# zeta2rework_lw_v24_fixes.net
KiCad netlist of a schematic drawn in EAGLE
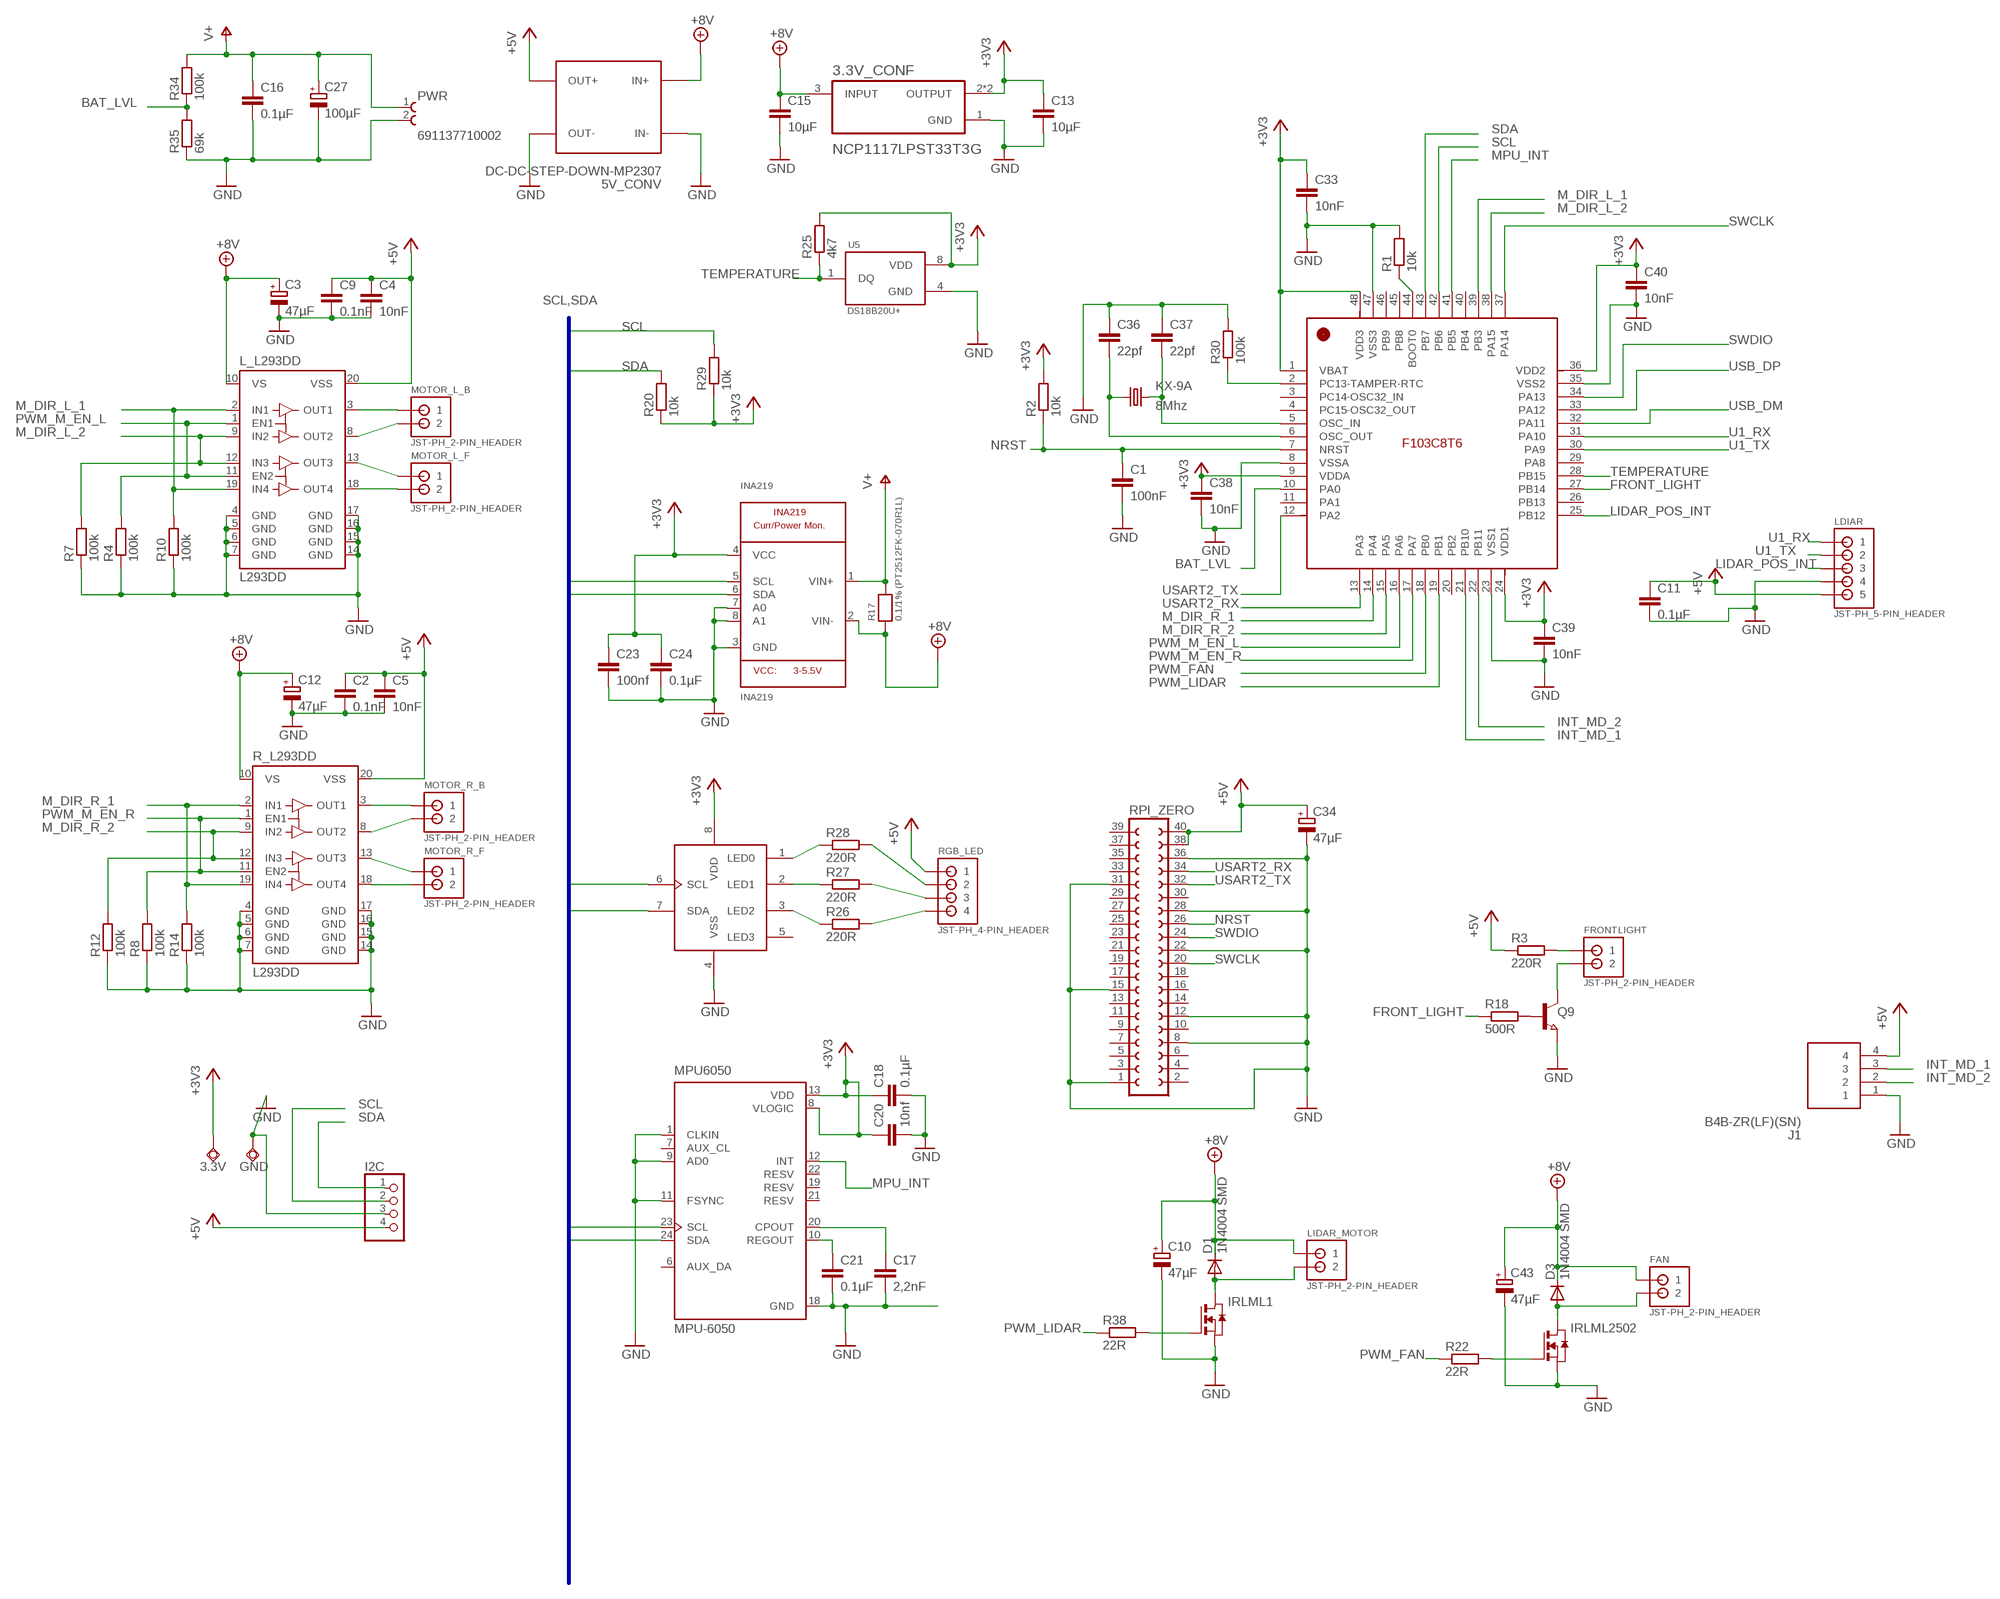
[diagram p0: schematic, sheet 1]

(export (version "E")
  (design (tool "Eeschema 10.0.6"))
  (components
    (comp (ref "3.3V")
      (value "TPSQTP20R")
      (footprint "eagle-import:TP20R")
      (libsource (lib "eagle-import") (part "TPSQTP20R"))
    )
    (comp (ref "3.3V_CONF")
      (value "NCP1117LPST33T3G")
      (footprint "eagle-import:SOT230P700X175-4N")
      (fields (field (name "MF") "ON Semiconductor"))
      (libsource (lib "eagle-import") (part "NCP1117LPST33T3G"))
    )
    (comp (ref "5V_CONV")
      (value "DC-DC-STEP-DOWN-MP2307")
      (footprint "eagle-import:DC-DC-STEP-DOWN-MP2307")
      (libsource (lib "eagle-import") (part "DC-DC-STEP-DOWN-MP2307"))
    )
    (comp (ref "C1")
      (value "100nF")
      (footprint "eagle-import:C1206")
      (libsource (lib "eagle-import") (part "C-EUC1206"))
    )
    (comp (ref "C2")
      (value "0.1nF")
      (footprint "eagle-import:C1206")
      (libsource (lib "eagle-import") (part "C-EUC1206"))
    )
    (comp (ref "C3")
      (value "47µF")
      (footprint "eagle-import:UD-4X5,8_NICHICON")
      (libsource (lib "eagle-import") (part "CPOL-EUUD-4X5,8"))
    )
    (comp (ref "C4")
      (value "10nF")
      (footprint "eagle-import:C1206")
      (libsource (lib "eagle-import") (part "C-EUC1206"))
    )
    (comp (ref "C5")
      (value "10nF")
      (footprint "eagle-import:C1206")
      (libsource (lib "eagle-import") (part "C-EUC1206"))
    )
    (comp (ref "C9")
      (value "0.1nF")
      (footprint "eagle-import:C1206")
      (libsource (lib "eagle-import") (part "C-EUC1206"))
    )
    (comp (ref "C10")
      (value "47µF")
      (footprint "eagle-import:UD-4X5,8_NICHICON")
      (libsource (lib "eagle-import") (part "CPOL-EUUD-4X5,8"))
    )
    (comp (ref "C11")
      (value "0.1µF")
      (footprint "eagle-import:C1206")
      (libsource (lib "eagle-import") (part "C-EUC1206"))
    )
    (comp (ref "C12")
      (value "47µF")
      (footprint "eagle-import:UD-4X5,8_NICHICON")
      (libsource (lib "eagle-import") (part "CPOL-EUUD-4X5,8"))
    )
    (comp (ref "C13")
      (value "10µF")
      (footprint "eagle-import:C1206")
      (libsource (lib "eagle-import") (part "C-EUC1206"))
    )
    (comp (ref "C15")
      (value "10µF")
      (footprint "eagle-import:C1206")
      (libsource (lib "eagle-import") (part "C-EUC1206"))
    )
    (comp (ref "C16")
      (value "0.1µF")
      (footprint "eagle-import:C1206")
      (libsource (lib "eagle-import") (part "C-EUC1206"))
    )
    (comp (ref "C17")
      (value "2,2nF")
      (footprint "eagle-import:C1206")
      (libsource (lib "eagle-import") (part "C-EUC1206"))
    )
    (comp (ref "C18")
      (value "0.1µF")
      (footprint "eagle-import:C1206")
      (libsource (lib "eagle-import") (part "C-EUC1206"))
    )
    (comp (ref "C20")
      (value "10nf")
      (footprint "eagle-import:C1206")
      (libsource (lib "eagle-import") (part "C-EUC1206"))
    )
    (comp (ref "C21")
      (value "0.1µF")
      (footprint "eagle-import:C1206")
      (libsource (lib "eagle-import") (part "C-EUC1206"))
    )
    (comp (ref "C23")
      (value "100nf")
      (footprint "eagle-import:C1206")
      (libsource (lib "eagle-import") (part "C-EUC1206"))
    )
    (comp (ref "C24")
      (value "0.1µF")
      (footprint "eagle-import:C1206")
      (libsource (lib "eagle-import") (part "C-EUC1206"))
    )
    (comp (ref "C27")
      (value "100µF")
      (footprint "eagle-import:UD-4X5,8_NICHICON")
      (libsource (lib "eagle-import") (part "CPOL-EUUD-4X5,8"))
    )
    (comp (ref "C33")
      (value "10nF")
      (footprint "eagle-import:C1206")
      (libsource (lib "eagle-import") (part "C-EUC1206"))
    )
    (comp (ref "C34")
      (value "47µF")
      (footprint "eagle-import:UD-4X5,8_NICHICON")
      (libsource (lib "eagle-import") (part "CPOL-EUUD-4X5,8"))
    )
    (comp (ref "C36")
      (value "22pf")
      (footprint "eagle-import:C1206")
      (libsource (lib "eagle-import") (part "C-EUC1206"))
    )
    (comp (ref "C37")
      (value "22pf")
      (footprint "eagle-import:C1206")
      (libsource (lib "eagle-import") (part "C-EUC1206"))
    )
    (comp (ref "C38")
      (value "10nF")
      (footprint "eagle-import:C1206")
      (libsource (lib "eagle-import") (part "C-EUC1206"))
    )
    (comp (ref "C39")
      (value "10nF")
      (footprint "eagle-import:C1206")
      (libsource (lib "eagle-import") (part "C-EUC1206"))
    )
    (comp (ref "C40")
      (value "10nF")
      (footprint "eagle-import:C1206")
      (libsource (lib "eagle-import") (part "C-EUC1206"))
    )
    (comp (ref "C43")
      (value "47µF")
      (footprint "eagle-import:UD-4X5,8_NICHICON")
      (libsource (lib "eagle-import") (part "CPOL-EUUD-4X5,8"))
    )
    (comp (ref "D1")
      (value "1N4004 SMD")
      (footprint "eagle-import:DO214AC")
      (libsource (lib "eagle-import") (part "DIODE-DO214AC"))
    )
    (comp (ref "D3")
      (value "1N4004 SMD")
      (footprint "eagle-import:DO214AC")
      (libsource (lib "eagle-import") (part "DIODE-DO214AC"))
    )
    (comp (ref "FAN")
      (value "JST-PH_2-PIN_HEADER")
      (footprint "eagle-import:JST_B2B-PH_HEADER")
      (libsource (lib "eagle-import") (part "JST-PH_2-PIN_HEADER"))
    )
    (comp (ref "FRONTLIGHT")
      (value "JST-PH_2-PIN_HEADER")
      (footprint "eagle-import:JST_B2B-PH_HEADER")
      (libsource (lib "eagle-import") (part "JST-PH_2-PIN_HEADER"))
    )
    (comp (ref "GND")
      (value "TPSQTP20R")
      (footprint "eagle-import:TP20R")
      (libsource (lib "eagle-import") (part "TPSQTP20R"))
    )
    (comp (ref "I2C")
      (value "PINHD-1X4")
      (footprint "eagle-import:1X04")
      (libsource (lib "eagle-import") (part "PINHD-1X4"))
    )
    (comp (ref "INA219")
      (value "INA219")
      (footprint "eagle-import:SOT23-8")
      (fields (field (name "MF") "Texas Instruments"))
      (libsource (lib "eagle-import") (part "INA219"))
    )
    (comp (ref "IRLML1")
      (value "NMOSSOT23")
      (footprint "eagle-import:SOT-23")
      (libsource (lib "eagle-import") (part "NMOSSOT23"))
    )
    (comp (ref "IRLML2502")
      (value "NMOSSOT23")
      (footprint "eagle-import:SOT-23")
      (libsource (lib "eagle-import") (part "NMOSSOT23"))
    )
    (comp (ref "J1")
      (value "B4B-ZR(LF)(SN)")
      (footprint "eagle-import:SHDR4W50P0X150_1X4_750X350X450")
      (fields (field (name "FARNELL_PART_NUMBER") "9491791"))
      (libsource (lib "eagle-import") (part "B4B-ZR(LF)(SN)"))
    )
    (comp (ref "KX-9A")
      (value "8Mhz")
      (footprint "eagle-import:5.0X3.2_KX-9A")
      (libsource (lib "eagle-import") (part "KX-9A"))
    )
    (comp (ref "LDIAR")
      (value "JST-PH_5-PIN_HEADER")
      (footprint "eagle-import:JST_B5B-PH_HEADER")
      (libsource (lib "eagle-import") (part "JST-PH_5-PIN_HEADER"))
    )
    (comp (ref "LIDAR_MOTOR")
      (value "JST-PH_2-PIN_HEADER")
      (footprint "eagle-import:JST_B2B-PH_HEADER")
      (libsource (lib "eagle-import") (part "JST-PH_2-PIN_HEADER"))
    )
    (comp (ref "L_L293DD")
      (value "L293DD")
      (footprint "eagle-import:SO20")
      (libsource (lib "eagle-import") (part "L293DD"))
    )
    (comp (ref "MOTOR_L_B")
      (value "JST-PH_2-PIN_HEADER")
      (footprint "eagle-import:JST_B2B-PH_HEADER")
      (libsource (lib "eagle-import") (part "JST-PH_2-PIN_HEADER"))
    )
    (comp (ref "MOTOR_L_F")
      (value "JST-PH_2-PIN_HEADER")
      (footprint "eagle-import:JST_B2B-PH_HEADER")
      (libsource (lib "eagle-import") (part "JST-PH_2-PIN_HEADER"))
    )
    (comp (ref "MOTOR_R_B")
      (value "JST-PH_2-PIN_HEADER")
      (footprint "eagle-import:JST_B2B-PH_HEADER")
      (libsource (lib "eagle-import") (part "JST-PH_2-PIN_HEADER"))
    )
    (comp (ref "MOTOR_R_F")
      (value "JST-PH_2-PIN_HEADER")
      (footprint "eagle-import:JST_B2B-PH_HEADER")
      (libsource (lib "eagle-import") (part "JST-PH_2-PIN_HEADER"))
    )
    (comp (ref "MPU6050")
      (value "MPU-6050")
      (footprint "eagle-import:QFN50P400X400X95-24N")
      (fields (field (name "MF") "TDK"))
      (libsource (lib "eagle-import") (part "MPU-6050"))
    )
    (comp (ref "PCA9533")
      (value "PCA9533")
      (footprint "eagle-import:SOIC8")
      (libsource (lib "eagle-import") (part "PCA9533"))
    )
    (comp (ref "PWR")
      (value "691137710002")
      (footprint "eagle-import:691137710002")
      (fields (field (name "MF") "Wurth Electronics"))
      (libsource (lib "eagle-import") (part "691137710002"))
    )
    (comp (ref "Q9")
      (value "NPN-TRANSISTOR_SOT23")
      (footprint "eagle-import:SOT23")
      (libsource (lib "eagle-import") (part "NPN-TRANSISTOR_SOT23"))
    )
    (comp (ref "R1")
      (value "10k")
      (footprint "eagle-import:R0603")
      (libsource (lib "eagle-import") (part "R-EU_R0603"))
    )
    (comp (ref "R2")
      (value "10k")
      (footprint "eagle-import:R0603")
      (libsource (lib "eagle-import") (part "R-EU_R0603"))
    )
    (comp (ref "R3")
      (value "220R")
      (footprint "eagle-import:R0603")
      (libsource (lib "eagle-import") (part "R-EU_R0603"))
    )
    (comp (ref "R4")
      (value "100k")
      (footprint "eagle-import:R0603")
      (libsource (lib "eagle-import") (part "R-EU_R0603"))
    )
    (comp (ref "R7")
      (value "100k")
      (footprint "eagle-import:R0603")
      (libsource (lib "eagle-import") (part "R-EU_R0603"))
    )
    (comp (ref "R8")
      (value "100k")
      (footprint "eagle-import:R0603")
      (libsource (lib "eagle-import") (part "R-EU_R0603"))
    )
    (comp (ref "R10")
      (value "100k")
      (footprint "eagle-import:R0603")
      (libsource (lib "eagle-import") (part "R-EU_R0603"))
    )
    (comp (ref "R12")
      (value "100k")
      (footprint "eagle-import:R0603")
      (libsource (lib "eagle-import") (part "R-EU_R0603"))
    )
    (comp (ref "R14")
      (value "100k")
      (footprint "eagle-import:R0603")
      (libsource (lib "eagle-import") (part "R-EU_R0603"))
    )
    (comp (ref "R17")
      (value "0.1/1% (PT2512FK-070R1L)")
      (footprint "eagle-import:2512")
      (libsource (lib "eagle-import") (part "RESISTOR2512"))
    )
    (comp (ref "R18")
      (value "500R")
      (footprint "eagle-import:R0603")
      (libsource (lib "eagle-import") (part "R-EU_R0603"))
    )
    (comp (ref "R20")
      (value "10k")
      (footprint "eagle-import:R0603")
      (libsource (lib "eagle-import") (part "R-EU_R0603"))
    )
    (comp (ref "R22")
      (value "22R")
      (footprint "eagle-import:R0603")
      (libsource (lib "eagle-import") (part "R-EU_R0603"))
    )
    (comp (ref "R25")
      (value "4k7")
      (footprint "eagle-import:R0603")
      (libsource (lib "eagle-import") (part "R-EU_R0603"))
    )
    (comp (ref "R26")
      (value "220R")
      (footprint "eagle-import:R0603")
      (libsource (lib "eagle-import") (part "R-EU_R0603"))
    )
    (comp (ref "R27")
      (value "220R")
      (footprint "eagle-import:R0603")
      (libsource (lib "eagle-import") (part "R-EU_R0603"))
    )
    (comp (ref "R28")
      (value "220R")
      (footprint "eagle-import:R0603")
      (libsource (lib "eagle-import") (part "R-EU_R0603"))
    )
    (comp (ref "R29")
      (value "10k")
      (footprint "eagle-import:R0603")
      (libsource (lib "eagle-import") (part "R-EU_R0603"))
    )
    (comp (ref "R30")
      (value "100k")
      (footprint "eagle-import:R0603")
      (libsource (lib "eagle-import") (part "R-EU_R0603"))
    )
    (comp (ref "R34")
      (value "100k")
      (footprint "eagle-import:R0603")
      (libsource (lib "eagle-import") (part "R-EU_R0603"))
    )
    (comp (ref "R35")
      (value "69k")
      (footprint "eagle-import:R0603")
      (libsource (lib "eagle-import") (part "R-EU_R0603"))
    )
    (comp (ref "R38")
      (value "22R")
      (footprint "eagle-import:R0603")
      (libsource (lib "eagle-import") (part "R-EU_R0603"))
    )
    (comp (ref "RGB_LED")
      (value "JST-PH_4-PIN_HEADER")
      (footprint "eagle-import:JST_B4B-PH_HEADER")
      (libsource (lib "eagle-import") (part "JST-PH_4-PIN_HEADER"))
    )
    (comp (ref "RPI_ZERO")
      (value "FE20-2")
      (footprint "eagle-import:FE20-2")
      (libsource (lib "eagle-import") (part "FE20-2"))
    )
    (comp (ref "R_L293DD")
      (value "L293DD")
      (footprint "eagle-import:SO20")
      (libsource (lib "eagle-import") (part "L293DD"))
    )
    (comp (ref "STM32F103CB")
      (value "STM32F103CB")
      (footprint "eagle-import:LQFP48_7X7MM_0.5MMPP")
      (fields (field (name "MF") "STMicroelectronics") (field (name "MP") "STM32F103C8T6"))
      (libsource (lib "eagle-import") (part "STM32F103C8T6"))
    )
    (comp (ref "U5")
      (value "DS18B20U+")
      (footprint "eagle-import:SOP65P490X95-8N")
      (fields (field (name "MF") "Maxim"))
      (libsource (lib "eagle-import") (part "DS18B20U+"))
    )
  )
  (nets
    (net (code "1") (name "+3V3") (class "Default")
      (node (ref "3.3V") (pin "TP") (pinfunction "TP_TP") (pintype "input"))
      (node (ref "3.3V_CONF") (pin "2") (pinfunction "OUTPUT_2") (pintype "output"))
      (node (ref "3.3V_CONF") (pin "4") (pinfunction "OUTPUT_4") (pintype "output"))
      (node (ref "C13") (pin "1") (pinfunction "1_1") (pintype "passive"))
      (node (ref "C18") (pin "1") (pinfunction "1_1") (pintype "passive"))
      (node (ref "C20") (pin "1") (pinfunction "1_1") (pintype "passive"))
      (node (ref "C23") (pin "1") (pinfunction "1_1") (pintype "passive"))
      (node (ref "C24") (pin "1") (pinfunction "1_1") (pintype "passive"))
      (node (ref "C33") (pin "1") (pinfunction "1_1") (pintype "passive"))
      (node (ref "C38") (pin "1") (pinfunction "1_1") (pintype "passive"))
      (node (ref "C39") (pin "1") (pinfunction "1_1") (pintype "passive"))
      (node (ref "C40") (pin "1") (pinfunction "1_1") (pintype "passive"))
      (node (ref "INA219") (pin "4") (pinfunction "VCC_4") (pintype "bidirectional"))
      (node (ref "MPU6050") (pin "13") (pinfunction "VDD_13") (pintype "power_in"))
      (node (ref "MPU6050") (pin "8") (pinfunction "VLOGIC_8") (pintype "power_in"))
      (node (ref "PCA9533") (pin "8") (pinfunction "VDD_8") (pintype "power_in"))
      (node (ref "R2") (pin "2") (pinfunction "2_2") (pintype "passive"))
      (node (ref "R20") (pin "1") (pinfunction "1_1") (pintype "passive"))
      (node (ref "R25") (pin "2") (pinfunction "2_2") (pintype "passive"))
      (node (ref "R29") (pin "1") (pinfunction "1_1") (pintype "passive"))
      (node (ref "STM32F103CB") (pin "1") (pinfunction "VBAT_1") (pintype "bidirectional"))
      (node (ref "STM32F103CB") (pin "24") (pinfunction "VDD1_24") (pintype "bidirectional"))
      (node (ref "STM32F103CB") (pin "36") (pinfunction "VDD2_36") (pintype "bidirectional"))
      (node (ref "STM32F103CB") (pin "48") (pinfunction "VDD3_48") (pintype "bidirectional"))
      (node (ref "STM32F103CB") (pin "9") (pinfunction "VDDA_9") (pintype "bidirectional"))
      (node (ref "U5") (pin "8") (pinfunction "VDD_8") (pintype "power_in"))
    )
    (net (code "2") (name "+5V") (class "Default")
      (node (ref "5V_CONV") (pin "OUT+") (pinfunction "OUT+_OUT+") (pintype "bidirectional"))
      (node (ref "C11") (pin "1") (pinfunction "1_1") (pintype "passive"))
      (node (ref "C2") (pin "1") (pinfunction "1_1") (pintype "passive"))
      (node (ref "C34") (pin "+") (pinfunction "+_+") (pintype "passive"))
      (node (ref "C4") (pin "1") (pinfunction "1_1") (pintype "passive"))
      (node (ref "C5") (pin "1") (pinfunction "1_1") (pintype "passive"))
      (node (ref "C9") (pin "1") (pinfunction "1_1") (pintype "passive"))
      (node (ref "I2C") (pin "4") (pinfunction "4_4") (pintype "passive"))
      (node (ref "J1") (pin "4") (pinfunction "4_4") (pintype "bidirectional"))
      (node (ref "LDIAR") (pin "P5") (pinfunction "5_P5") (pintype "bidirectional"))
      (node (ref "L_L293DD") (pin "20") (pinfunction "VSS_20") (pintype "power_in"))
      (node (ref "R3") (pin "1") (pinfunction "1_1") (pintype "passive"))
      (node (ref "RGB_LED") (pin "P1") (pinfunction "1_P1") (pintype "bidirectional"))
      (node (ref "RPI_ZERO") (pin "38") (pinfunction "38_38") (pintype "passive"))
      (node (ref "RPI_ZERO") (pin "40") (pinfunction "40_40") (pintype "passive"))
      (node (ref "R_L293DD") (pin "20") (pinfunction "VSS_20") (pintype "power_in"))
    )
    (net (code "3") (name "+8V") (class "Default")
      (node (ref "3.3V_CONF") (pin "3") (pinfunction "INPUT_3") (pintype "input"))
      (node (ref "5V_CONV") (pin "IN+") (pinfunction "IN+_IN+") (pintype "bidirectional"))
      (node (ref "C10") (pin "+") (pinfunction "+_+") (pintype "passive"))
      (node (ref "C12") (pin "+") (pinfunction "+_+") (pintype "passive"))
      (node (ref "C15") (pin "1") (pinfunction "1_1") (pintype "passive"))
      (node (ref "C3") (pin "+") (pinfunction "+_+") (pintype "passive"))
      (node (ref "C43") (pin "+") (pinfunction "+_+") (pintype "passive"))
      (node (ref "D1") (pin "C") (pinfunction "C_C") (pintype "passive"))
      (node (ref "D3") (pin "C") (pinfunction "C_C") (pintype "passive"))
      (node (ref "FAN") (pin "P1") (pinfunction "1_P1") (pintype "bidirectional"))
      (node (ref "INA219") (pin "2") (pinfunction "VIN-_2") (pintype "bidirectional"))
      (node (ref "LIDAR_MOTOR") (pin "P1") (pinfunction "1_P1") (pintype "bidirectional"))
      (node (ref "L_L293DD") (pin "10") (pinfunction "VS_10") (pintype "power_in"))
      (node (ref "R17") (pin "1") (pinfunction "1_1") (pintype "passive"))
      (node (ref "R_L293DD") (pin "10") (pinfunction "VS_10") (pintype "power_in"))
    )
    (net (code "4") (name "/BAT_LVL") (class "Default")
      (node (ref "R34") (pin "1") (pinfunction "1_1") (pintype "passive"))
      (node (ref "R35") (pin "2") (pinfunction "2_2") (pintype "passive"))
      (node (ref "STM32F103CB") (pin "10") (pinfunction "PA0_10") (pintype "bidirectional"))
    )
    (net (code "5") (name "/FRONT_LIGHT") (class "Default")
      (node (ref "R18") (pin "1") (pinfunction "1_1") (pintype "passive"))
      (node (ref "STM32F103CB") (pin "27") (pinfunction "PB14_27") (pintype "bidirectional"))
    )
    (net (code "6") (name "/INT_MD_1") (class "Default")
      (node (ref "J1") (pin "3") (pinfunction "3_3") (pintype "bidirectional"))
      (node (ref "STM32F103CB") (pin "21") (pinfunction "PB10_21") (pintype "bidirectional"))
    )
    (net (code "7") (name "/INT_MD_2") (class "Default")
      (node (ref "J1") (pin "2") (pinfunction "2_2") (pintype "bidirectional"))
      (node (ref "STM32F103CB") (pin "22") (pinfunction "PB11_22") (pintype "bidirectional"))
    )
    (net (code "8") (name "/LIDAR_POS_INT") (class "Default")
      (node (ref "LDIAR") (pin "P3") (pinfunction "3_P3") (pintype "bidirectional"))
      (node (ref "STM32F103CB") (pin "25") (pinfunction "PB12_25") (pintype "bidirectional"))
    )
    (net (code "9") (name "/MPU_INT") (class "Default")
      (node (ref "MPU6050") (pin "12") (pinfunction "INT_12") (pintype "output"))
      (node (ref "STM32F103CB") (pin "41") (pinfunction "PB5_41") (pintype "bidirectional"))
    )
    (net (code "10") (name "/M_DIR_L_1") (class "Default")
      (node (ref "L_L293DD") (pin "19") (pinfunction "IN4_19") (pintype "input"))
      (node (ref "L_L293DD") (pin "2") (pinfunction "IN1_2") (pintype "input"))
      (node (ref "R10") (pin "2") (pinfunction "2_2") (pintype "passive"))
      (node (ref "STM32F103CB") (pin "39") (pinfunction "PB3_39") (pintype "bidirectional"))
    )
    (net (code "11") (name "/M_DIR_L_2") (class "Default")
      (node (ref "L_L293DD") (pin "12") (pinfunction "IN3_12") (pintype "input"))
      (node (ref "L_L293DD") (pin "9") (pinfunction "IN2_9") (pintype "input"))
      (node (ref "R7") (pin "2") (pinfunction "2_2") (pintype "passive"))
      (node (ref "STM32F103CB") (pin "38") (pinfunction "PA15_38") (pintype "bidirectional"))
    )
    (net (code "12") (name "/M_DIR_R_1") (class "Default")
      (node (ref "R14") (pin "2") (pinfunction "2_2") (pintype "passive"))
      (node (ref "R_L293DD") (pin "19") (pinfunction "IN4_19") (pintype "input"))
      (node (ref "R_L293DD") (pin "2") (pinfunction "IN1_2") (pintype "input"))
      (node (ref "STM32F103CB") (pin "14") (pinfunction "PA4_14") (pintype "bidirectional"))
    )
    (net (code "13") (name "/M_DIR_R_2") (class "Default")
      (node (ref "R12") (pin "2") (pinfunction "2_2") (pintype "passive"))
      (node (ref "R_L293DD") (pin "12") (pinfunction "IN3_12") (pintype "input"))
      (node (ref "R_L293DD") (pin "9") (pinfunction "IN2_9") (pintype "input"))
      (node (ref "STM32F103CB") (pin "15") (pinfunction "PA5_15") (pintype "bidirectional"))
    )
    (net (code "14") (name "/NRST") (class "Default")
      (node (ref "C1") (pin "1") (pinfunction "1_1") (pintype "passive"))
      (node (ref "R2") (pin "1") (pinfunction "1_1") (pintype "passive"))
      (node (ref "RPI_ZERO") (pin "26") (pinfunction "26_26") (pintype "passive"))
      (node (ref "STM32F103CB") (pin "7") (pinfunction "NRST_7") (pintype "bidirectional"))
    )
    (net (code "15") (name "/PWM_FAN") (class "Default")
      (node (ref "R22") (pin "1") (pinfunction "1_1") (pintype "passive"))
      (node (ref "STM32F103CB") (pin "18") (pinfunction "PB0_18") (pintype "bidirectional"))
    )
    (net (code "16") (name "/PWM_LIDAR") (class "Default")
      (node (ref "R38") (pin "1") (pinfunction "1_1") (pintype "passive"))
      (node (ref "STM32F103CB") (pin "19") (pinfunction "PB1_19") (pintype "bidirectional"))
    )
    (net (code "17") (name "/PWM_M_EN_L") (class "Default")
      (node (ref "L_L293DD") (pin "1") (pinfunction "EN1_1") (pintype "input"))
      (node (ref "L_L293DD") (pin "11") (pinfunction "EN2_11") (pintype "input"))
      (node (ref "R4") (pin "2") (pinfunction "2_2") (pintype "passive"))
      (node (ref "STM32F103CB") (pin "16") (pinfunction "PA6_16") (pintype "bidirectional"))
    )
    (net (code "18") (name "/PWM_M_EN_R") (class "Default")
      (node (ref "R8") (pin "2") (pinfunction "2_2") (pintype "passive"))
      (node (ref "R_L293DD") (pin "1") (pinfunction "EN1_1") (pintype "input"))
      (node (ref "R_L293DD") (pin "11") (pinfunction "EN2_11") (pintype "input"))
      (node (ref "STM32F103CB") (pin "17") (pinfunction "PA7_17") (pintype "bidirectional"))
    )
    (net (code "19") (name "/SCL") (class "Default")
      (node (ref "I2C") (pin "2") (pinfunction "2_2") (pintype "passive"))
      (node (ref "INA219") (pin "5") (pinfunction "SCL_5") (pintype "bidirectional"))
      (node (ref "MPU6050") (pin "23") (pinfunction "SCL_23") (pintype "input"))
      (node (ref "PCA9533") (pin "6") (pinfunction "SCL_6") (pintype "input"))
      (node (ref "R29") (pin "2") (pinfunction "2_2") (pintype "passive"))
      (node (ref "STM32F103CB") (pin "42") (pinfunction "PB6_42") (pintype "bidirectional"))
    )
    (net (code "20") (name "/SDA") (class "Default")
      (node (ref "I2C") (pin "1") (pinfunction "1_1") (pintype "passive"))
      (node (ref "INA219") (pin "6") (pinfunction "SDA_6") (pintype "bidirectional"))
      (node (ref "MPU6050") (pin "24") (pinfunction "SDA_24") (pintype "bidirectional"))
      (node (ref "PCA9533") (pin "7") (pinfunction "SDA_7") (pintype "bidirectional"))
      (node (ref "R20") (pin "2") (pinfunction "2_2") (pintype "passive"))
      (node (ref "STM32F103CB") (pin "43") (pinfunction "PB7_43") (pintype "bidirectional"))
    )
    (net (code "21") (name "/SWCLK") (class "Default")
      (node (ref "RPI_ZERO") (pin "20") (pinfunction "20_20") (pintype "passive"))
      (node (ref "STM32F103CB") (pin "37") (pinfunction "PA14_37") (pintype "bidirectional"))
    )
    (net (code "22") (name "/SWDIO") (class "Default")
      (node (ref "RPI_ZERO") (pin "24") (pinfunction "24_24") (pintype "passive"))
      (node (ref "STM32F103CB") (pin "34") (pinfunction "PA13_34") (pintype "bidirectional"))
    )
    (net (code "23") (name "/TEMPERATURE") (class "Default")
      (node (ref "R25") (pin "1") (pinfunction "1_1") (pintype "passive"))
      (node (ref "STM32F103CB") (pin "28") (pinfunction "PB15_28") (pintype "bidirectional"))
      (node (ref "U5") (pin "1") (pinfunction "DQ_1") (pintype "bidirectional"))
    )
    (net (code "24") (name "/U1_RX") (class "Default")
      (node (ref "LDIAR") (pin "P1") (pinfunction "1_P1") (pintype "bidirectional"))
      (node (ref "STM32F103CB") (pin "31") (pinfunction "PA10_31") (pintype "bidirectional"))
    )
    (net (code "25") (name "/U1_TX") (class "Default")
      (node (ref "LDIAR") (pin "P2") (pinfunction "2_P2") (pintype "bidirectional"))
      (node (ref "STM32F103CB") (pin "30") (pinfunction "PA9_30") (pintype "bidirectional"))
    )
    (net (code "26") (name "/USART2_RX") (class "Default")
      (node (ref "RPI_ZERO") (pin "34") (pinfunction "34_34") (pintype "passive"))
      (node (ref "STM32F103CB") (pin "13") (pinfunction "PA3_13") (pintype "bidirectional"))
    )
    (net (code "27") (name "/USART2_TX") (class "Default")
      (node (ref "RPI_ZERO") (pin "32") (pinfunction "32_32") (pintype "passive"))
      (node (ref "STM32F103CB") (pin "12") (pinfunction "PA2_12") (pintype "bidirectional"))
    )
    (net (code "28") (name "/USB_DM") (class "Default")
      (node (ref "STM32F103CB") (pin "32") (pinfunction "PA11_32") (pintype "bidirectional"))
    )
    (net (code "29") (name "/USB_DP") (class "Default")
      (node (ref "STM32F103CB") (pin "33") (pinfunction "PA12_33") (pintype "bidirectional"))
    )
    (net (code "31") (name "GND") (class "Default")
      (node (ref "3.3V_CONF") (pin "1") (pinfunction "GND_1") (pintype "power_in"))
      (node (ref "5V_CONV") (pin "IN-") (pinfunction "IN-_IN-") (pintype "bidirectional"))
      (node (ref "5V_CONV") (pin "OUT-") (pinfunction "OUT-_OUT-") (pintype "bidirectional"))
      (node (ref "C1") (pin "2") (pinfunction "2_2") (pintype "passive"))
      (node (ref "C10") (pin "-") (pinfunction "-_-") (pintype "passive"))
      (node (ref "C11") (pin "2") (pinfunction "2_2") (pintype "passive"))
      (node (ref "C12") (pin "-") (pinfunction "-_-") (pintype "passive"))
      (node (ref "C13") (pin "2") (pinfunction "2_2") (pintype "passive"))
      (node (ref "C15") (pin "2") (pinfunction "2_2") (pintype "passive"))
      (node (ref "C16") (pin "2") (pinfunction "2_2") (pintype "passive"))
      (node (ref "C17") (pin "2") (pinfunction "2_2") (pintype "passive"))
      (node (ref "C18") (pin "2") (pinfunction "2_2") (pintype "passive"))
      (node (ref "C2") (pin "2") (pinfunction "2_2") (pintype "passive"))
      (node (ref "C20") (pin "2") (pinfunction "2_2") (pintype "passive"))
      (node (ref "C21") (pin "2") (pinfunction "2_2") (pintype "passive"))
      (node (ref "C23") (pin "2") (pinfunction "2_2") (pintype "passive"))
      (node (ref "C24") (pin "2") (pinfunction "2_2") (pintype "passive"))
      (node (ref "C27") (pin "-") (pinfunction "-_-") (pintype "passive"))
      (node (ref "C3") (pin "-") (pinfunction "-_-") (pintype "passive"))
      (node (ref "C33") (pin "2") (pinfunction "2_2") (pintype "passive"))
      (node (ref "C34") (pin "-") (pinfunction "-_-") (pintype "passive"))
      (node (ref "C36") (pin "1") (pinfunction "1_1") (pintype "passive"))
      (node (ref "C37") (pin "1") (pinfunction "1_1") (pintype "passive"))
      (node (ref "C38") (pin "2") (pinfunction "2_2") (pintype "passive"))
      (node (ref "C39") (pin "2") (pinfunction "2_2") (pintype "passive"))
      (node (ref "C4") (pin "2") (pinfunction "2_2") (pintype "passive"))
      (node (ref "C40") (pin "2") (pinfunction "2_2") (pintype "passive"))
      (node (ref "C43") (pin "-") (pinfunction "-_-") (pintype "passive"))
      (node (ref "C5") (pin "2") (pinfunction "2_2") (pintype "passive"))
      (node (ref "C9") (pin "2") (pinfunction "2_2") (pintype "passive"))
      (node (ref "GND") (pin "TP") (pinfunction "TP_TP") (pintype "input"))
      (node (ref "I2C") (pin "3") (pinfunction "3_3") (pintype "passive"))
      (node (ref "INA219") (pin "3") (pinfunction "GND_3") (pintype "bidirectional"))
      (node (ref "INA219") (pin "7") (pinfunction "A0_7") (pintype "bidirectional"))
      (node (ref "INA219") (pin "8") (pinfunction "A1_8") (pintype "bidirectional"))
      (node (ref "IRLML1") (pin "2") (pinfunction "S_2") (pintype "passive"))
      (node (ref "IRLML2502") (pin "2") (pinfunction "S_2") (pintype "passive"))
      (node (ref "J1") (pin "1") (pinfunction "1_1") (pintype "bidirectional"))
      (node (ref "LDIAR") (pin "P4") (pinfunction "4_P4") (pintype "bidirectional"))
      (node (ref "L_L293DD") (pin "14") (pinfunction "GND_14") (pintype "power_in"))
      (node (ref "L_L293DD") (pin "15") (pinfunction "GND_15") (pintype "power_in"))
      (node (ref "L_L293DD") (pin "16") (pinfunction "GND_16") (pintype "power_in"))
      (node (ref "L_L293DD") (pin "17") (pinfunction "GND_17") (pintype "power_in"))
      (node (ref "L_L293DD") (pin "4") (pinfunction "GND_4") (pintype "power_in"))
      (node (ref "L_L293DD") (pin "5") (pinfunction "GND_5") (pintype "power_in"))
      (node (ref "L_L293DD") (pin "6") (pinfunction "GND_6") (pintype "power_in"))
      (node (ref "L_L293DD") (pin "7") (pinfunction "GND_7") (pintype "power_in"))
      (node (ref "MPU6050") (pin "1") (pinfunction "CLKIN_1") (pintype "input"))
      (node (ref "MPU6050") (pin "11") (pinfunction "FSYNC_11") (pintype "input"))
      (node (ref "MPU6050") (pin "18") (pinfunction "GND_18") (pintype "power_in"))
      (node (ref "MPU6050") (pin "9") (pinfunction "AD0_9") (pintype "input"))
      (node (ref "PCA9533") (pin "4") (pinfunction "VSS_4") (pintype "power_in"))
      (node (ref "PWR") (pin "2") (pinfunction "2_2") (pintype "passive"))
      (node (ref "Q9") (pin "2") (pinfunction "E_2") (pintype "passive"))
      (node (ref "R1") (pin "2") (pinfunction "2_2") (pintype "passive"))
      (node (ref "R10") (pin "1") (pinfunction "1_1") (pintype "passive"))
      (node (ref "R12") (pin "1") (pinfunction "1_1") (pintype "passive"))
      (node (ref "R14") (pin "1") (pinfunction "1_1") (pintype "passive"))
      (node (ref "R30") (pin "2") (pinfunction "2_2") (pintype "passive"))
      (node (ref "R35") (pin "1") (pinfunction "1_1") (pintype "passive"))
      (node (ref "R4") (pin "1") (pinfunction "1_1") (pintype "passive"))
      (node (ref "R7") (pin "1") (pinfunction "1_1") (pintype "passive"))
      (node (ref "R8") (pin "1") (pinfunction "1_1") (pintype "passive"))
      (node (ref "RPI_ZERO") (pin "1") (pinfunction "1_1") (pintype "passive"))
      (node (ref "RPI_ZERO") (pin "12") (pinfunction "12_12") (pintype "passive"))
      (node (ref "RPI_ZERO") (pin "15") (pinfunction "15_15") (pintype "passive"))
      (node (ref "RPI_ZERO") (pin "22") (pinfunction "22_22") (pintype "passive"))
      (node (ref "RPI_ZERO") (pin "28") (pinfunction "28_28") (pintype "passive"))
      (node (ref "RPI_ZERO") (pin "31") (pinfunction "31_31") (pintype "passive"))
      (node (ref "RPI_ZERO") (pin "36") (pinfunction "36_36") (pintype "passive"))
      (node (ref "RPI_ZERO") (pin "8") (pinfunction "8_8") (pintype "passive"))
      (node (ref "R_L293DD") (pin "14") (pinfunction "GND_14") (pintype "power_in"))
      (node (ref "R_L293DD") (pin "15") (pinfunction "GND_15") (pintype "power_in"))
      (node (ref "R_L293DD") (pin "16") (pinfunction "GND_16") (pintype "power_in"))
      (node (ref "R_L293DD") (pin "17") (pinfunction "GND_17") (pintype "power_in"))
      (node (ref "R_L293DD") (pin "4") (pinfunction "GND_4") (pintype "power_in"))
      (node (ref "R_L293DD") (pin "5") (pinfunction "GND_5") (pintype "power_in"))
      (node (ref "R_L293DD") (pin "6") (pinfunction "GND_6") (pintype "power_in"))
      (node (ref "R_L293DD") (pin "7") (pinfunction "GND_7") (pintype "power_in"))
      (node (ref "STM32F103CB") (pin "23") (pinfunction "VSS1_23") (pintype "bidirectional"))
      (node (ref "STM32F103CB") (pin "35") (pinfunction "VSS2_35") (pintype "bidirectional"))
      (node (ref "STM32F103CB") (pin "47") (pinfunction "VSS3_47") (pintype "bidirectional"))
      (node (ref "STM32F103CB") (pin "8") (pinfunction "VSSA_8") (pintype "bidirectional"))
      (node (ref "U5") (pin "4") (pinfunction "GND_4") (pintype "power_in"))
    )
    (net (code "32") (name "Net-(FAN-2)") (class "Default")
      (node (ref "D3") (pin "A") (pinfunction "A_A") (pintype "passive"))
      (node (ref "FAN") (pin "P2") (pinfunction "2_P2") (pintype "bidirectional"))
      (node (ref "IRLML2502") (pin "1") (pinfunction "D_1") (pintype "passive"))
    )
    (net (code "33") (name "Net-(FRONTLIGHT-1)") (class "Default")
      (node (ref "FRONTLIGHT") (pin "P1") (pinfunction "1_P1") (pintype "bidirectional"))
      (node (ref "R3") (pin "2") (pinfunction "2_2") (pintype "passive"))
    )
    (net (code "34") (name "Net-(FRONTLIGHT-2)") (class "Default")
      (node (ref "FRONTLIGHT") (pin "P2") (pinfunction "2_P2") (pintype "bidirectional"))
      (node (ref "Q9") (pin "3") (pinfunction "C_3") (pintype "passive"))
    )
    (net (code "35") (name "Net-(IRLML1-D)") (class "Default")
      (node (ref "D1") (pin "A") (pinfunction "A_A") (pintype "passive"))
      (node (ref "IRLML1") (pin "1") (pinfunction "D_1") (pintype "passive"))
      (node (ref "LIDAR_MOTOR") (pin "P2") (pinfunction "2_P2") (pintype "bidirectional"))
    )
    (net (code "36") (name "Net-(IRLML1-G)") (class "Default")
      (node (ref "IRLML1") (pin "3") (pinfunction "G_3") (pintype "passive"))
      (node (ref "R38") (pin "2") (pinfunction "2_2") (pintype "passive"))
    )
    (net (code "37") (name "Net-(IRLML2502-G)") (class "Default")
      (node (ref "IRLML2502") (pin "3") (pinfunction "G_3") (pintype "passive"))
      (node (ref "R22") (pin "2") (pinfunction "2_2") (pintype "passive"))
    )
    (net (code "38") (name "Net-(KX-9A-2)") (class "Default")
      (node (ref "C37") (pin "2") (pinfunction "2_2") (pintype "passive"))
      (node (ref "KX-9A") (pin "3") (pinfunction "2_3") (pintype "passive"))
      (node (ref "STM32F103CB") (pin "5") (pinfunction "OSC_IN_5") (pintype "bidirectional"))
    )
    (net (code "39") (name "Net-(L_L293DD-OUT1)") (class "Default")
      (node (ref "L_L293DD") (pin "3") (pinfunction "OUT1_3") (pintype "output"))
      (node (ref "MOTOR_L_B") (pin "P1") (pinfunction "1_P1") (pintype "bidirectional"))
    )
    (net (code "40") (name "Net-(L_L293DD-OUT2)") (class "Default")
      (node (ref "L_L293DD") (pin "8") (pinfunction "OUT2_8") (pintype "output"))
      (node (ref "MOTOR_L_B") (pin "P2") (pinfunction "2_P2") (pintype "bidirectional"))
    )
    (net (code "41") (name "Net-(L_L293DD-OUT3)") (class "Default")
      (node (ref "L_L293DD") (pin "13") (pinfunction "OUT3_13") (pintype "output"))
      (node (ref "MOTOR_L_F") (pin "P1") (pinfunction "1_P1") (pintype "bidirectional"))
    )
    (net (code "42") (name "Net-(L_L293DD-OUT4)") (class "Default")
      (node (ref "L_L293DD") (pin "18") (pinfunction "OUT4_18") (pintype "output"))
      (node (ref "MOTOR_L_F") (pin "P2") (pinfunction "2_P2") (pintype "bidirectional"))
    )
    (net (code "43") (name "Net-(MOTOR_R_B-1)") (class "Default")
      (node (ref "MOTOR_R_B") (pin "P1") (pinfunction "1_P1") (pintype "bidirectional"))
      (node (ref "R_L293DD") (pin "3") (pinfunction "OUT1_3") (pintype "output"))
    )
    (net (code "44") (name "Net-(MOTOR_R_B-2)") (class "Default")
      (node (ref "MOTOR_R_B") (pin "P2") (pinfunction "2_P2") (pintype "bidirectional"))
      (node (ref "R_L293DD") (pin "8") (pinfunction "OUT2_8") (pintype "output"))
    )
    (net (code "45") (name "Net-(MOTOR_R_F-1)") (class "Default")
      (node (ref "MOTOR_R_F") (pin "P1") (pinfunction "1_P1") (pintype "bidirectional"))
      (node (ref "R_L293DD") (pin "13") (pinfunction "OUT3_13") (pintype "output"))
    )
    (net (code "46") (name "Net-(MOTOR_R_F-2)") (class "Default")
      (node (ref "MOTOR_R_F") (pin "P2") (pinfunction "2_P2") (pintype "bidirectional"))
      (node (ref "R_L293DD") (pin "18") (pinfunction "OUT4_18") (pintype "output"))
    )
    (net (code "47") (name "Net-(MPU6050-CPOUT)") (class "Default")
      (node (ref "C17") (pin "1") (pinfunction "1_1") (pintype "passive"))
      (node (ref "MPU6050") (pin "20") (pinfunction "CPOUT_20") (pintype "passive"))
    )
    (net (code "48") (name "Net-(MPU6050-REGOUT)") (class "Default")
      (node (ref "C21") (pin "1") (pinfunction "1_1") (pintype "passive"))
      (node (ref "MPU6050") (pin "10") (pinfunction "REGOUT_10") (pintype "passive"))
    )
    (net (code "49") (name "Net-(PCA9533-LED0)") (class "Default")
      (node (ref "PCA9533") (pin "1") (pinfunction "LED0_1") (pintype "bidirectional"))
      (node (ref "R28") (pin "1") (pinfunction "1_1") (pintype "passive"))
    )
    (net (code "50") (name "Net-(PCA9533-LED1)") (class "Default")
      (node (ref "PCA9533") (pin "2") (pinfunction "LED1_2") (pintype "bidirectional"))
      (node (ref "R27") (pin "1") (pinfunction "1_1") (pintype "passive"))
    )
    (net (code "51") (name "Net-(PCA9533-LED2)") (class "Default")
      (node (ref "PCA9533") (pin "3") (pinfunction "LED2_3") (pintype "bidirectional"))
      (node (ref "R26") (pin "1") (pinfunction "1_1") (pintype "passive"))
    )
    (net (code "52") (name "Net-(Q9-B)") (class "Default")
      (node (ref "Q9") (pin "1") (pinfunction "B_1") (pintype "passive"))
      (node (ref "R18") (pin "2") (pinfunction "2_2") (pintype "passive"))
    )
    (net (code "53") (name "Net-(RGB_LED-2)") (class "Default")
      (node (ref "R28") (pin "2") (pinfunction "2_2") (pintype "passive"))
      (node (ref "RGB_LED") (pin "P2") (pinfunction "2_P2") (pintype "bidirectional"))
    )
    (net (code "54") (name "Net-(RGB_LED-3)") (class "Default")
      (node (ref "R27") (pin "2") (pinfunction "2_2") (pintype "passive"))
      (node (ref "RGB_LED") (pin "P3") (pinfunction "3_P3") (pintype "bidirectional"))
    )
    (net (code "55") (name "Net-(RGB_LED-4)") (class "Default")
      (node (ref "R26") (pin "2") (pinfunction "2_2") (pintype "passive"))
      (node (ref "RGB_LED") (pin "P4") (pinfunction "4_P4") (pintype "bidirectional"))
    )
    (net (code "56") (name "Net-(STM32F103CB-BOOT0)") (class "Default")
      (node (ref "R1") (pin "1") (pinfunction "1_1") (pintype "passive"))
      (node (ref "STM32F103CB") (pin "44") (pinfunction "BOOT0_44") (pintype "bidirectional"))
    )
    (net (code "57") (name "Net-(STM32F103CB-OSC_OUT)") (class "Default")
      (node (ref "C36") (pin "2") (pinfunction "2_2") (pintype "passive"))
      (node (ref "KX-9A") (pin "1") (pinfunction "1_1") (pintype "passive"))
      (node (ref "STM32F103CB") (pin "6") (pinfunction "OSC_OUT_6") (pintype "bidirectional"))
    )
    (net (code "58") (name "Net-(STM32F103CB-PC13-TAMPER-RTC)") (class "Default")
      (node (ref "R30") (pin "1") (pinfunction "1_1") (pintype "passive"))
      (node (ref "STM32F103CB") (pin "2") (pinfunction "PC13-TAMPER-RTC_2") (pintype "bidirectional"))
    )
    (net (code "59") (name "V+") (class "Default")
      (node (ref "C16") (pin "1") (pinfunction "1_1") (pintype "passive"))
      (node (ref "C27") (pin "+") (pinfunction "+_+") (pintype "passive"))
      (node (ref "INA219") (pin "1") (pinfunction "VIN+_1") (pintype "bidirectional"))
      (node (ref "PWR") (pin "1") (pinfunction "1_1") (pintype "passive"))
      (node (ref "R17") (pin "2") (pinfunction "2_2") (pintype "passive"))
      (node (ref "R34") (pin "2") (pinfunction "2_2") (pintype "passive"))
    )
    (net (code "60") (name "unconnected-(MPU6050-AUX_CL-Pad7)") (class "Default")
      (node (ref "MPU6050") (pin "7") (pinfunction "AUX_CL_7") (pintype "input"))
    )
    (net (code "61") (name "unconnected-(MPU6050-AUX_DA-Pad6)") (class "Default")
      (node (ref "MPU6050") (pin "6") (pinfunction "AUX_DA_6") (pintype "bidirectional"))
    )
    (net (code "62") (name "unconnected-(MPU6050-RESV-Pad19)") (class "Default")
      (node (ref "MPU6050") (pin "19") (pinfunction "RESV_19") (pintype "passive"))
    )
    (net (code "63") (name "unconnected-(MPU6050-RESV-Pad21)") (class "Default")
      (node (ref "MPU6050") (pin "21") (pinfunction "RESV_21") (pintype "passive"))
    )
    (net (code "64") (name "unconnected-(MPU6050-RESV-Pad22)") (class "Default")
      (node (ref "MPU6050") (pin "22") (pinfunction "RESV_22") (pintype "passive"))
    )
    (net (code "65") (name "unconnected-(PCA9533-LED3-Pad5)") (class "Default")
      (node (ref "PCA9533") (pin "5") (pinfunction "LED3_5") (pintype "bidirectional"))
    )
    (net (code "66") (name "unconnected-(RPI_ZERO-Pad2)") (class "Default")
      (node (ref "RPI_ZERO") (pin "2") (pinfunction "2_2") (pintype "passive"))
    )
    (net (code "67") (name "unconnected-(RPI_ZERO-Pad3)") (class "Default")
      (node (ref "RPI_ZERO") (pin "3") (pinfunction "3_3") (pintype "passive"))
    )
    (net (code "68") (name "unconnected-(RPI_ZERO-Pad4)") (class "Default")
      (node (ref "RPI_ZERO") (pin "4") (pinfunction "4_4") (pintype "passive"))
    )
    (net (code "69") (name "unconnected-(RPI_ZERO-Pad5)") (class "Default")
      (node (ref "RPI_ZERO") (pin "5") (pinfunction "5_5") (pintype "passive"))
    )
    (net (code "70") (name "unconnected-(RPI_ZERO-Pad6)") (class "Default")
      (node (ref "RPI_ZERO") (pin "6") (pinfunction "6_6") (pintype "passive"))
    )
    (net (code "71") (name "unconnected-(RPI_ZERO-Pad7)") (class "Default")
      (node (ref "RPI_ZERO") (pin "7") (pinfunction "7_7") (pintype "passive"))
    )
    (net (code "72") (name "unconnected-(RPI_ZERO-Pad9)") (class "Default")
      (node (ref "RPI_ZERO") (pin "9") (pinfunction "9_9") (pintype "passive"))
    )
    (net (code "73") (name "unconnected-(RPI_ZERO-Pad10)") (class "Default")
      (node (ref "RPI_ZERO") (pin "10") (pinfunction "10_10") (pintype "passive"))
    )
    (net (code "74") (name "unconnected-(RPI_ZERO-Pad11)") (class "Default")
      (node (ref "RPI_ZERO") (pin "11") (pinfunction "11_11") (pintype "passive"))
    )
    (net (code "75") (name "unconnected-(RPI_ZERO-Pad13)") (class "Default")
      (node (ref "RPI_ZERO") (pin "13") (pinfunction "13_13") (pintype "passive"))
    )
    (net (code "76") (name "unconnected-(RPI_ZERO-Pad14)") (class "Default")
      (node (ref "RPI_ZERO") (pin "14") (pinfunction "14_14") (pintype "passive"))
    )
    (net (code "77") (name "unconnected-(RPI_ZERO-Pad16)") (class "Default")
      (node (ref "RPI_ZERO") (pin "16") (pinfunction "16_16") (pintype "passive"))
    )
    (net (code "78") (name "unconnected-(RPI_ZERO-Pad17)") (class "Default")
      (node (ref "RPI_ZERO") (pin "17") (pinfunction "17_17") (pintype "passive"))
    )
    (net (code "79") (name "unconnected-(RPI_ZERO-Pad18)") (class "Default")
      (node (ref "RPI_ZERO") (pin "18") (pinfunction "18_18") (pintype "passive"))
    )
    (net (code "80") (name "unconnected-(RPI_ZERO-Pad19)") (class "Default")
      (node (ref "RPI_ZERO") (pin "19") (pinfunction "19_19") (pintype "passive"))
    )
    (net (code "81") (name "unconnected-(RPI_ZERO-Pad21)") (class "Default")
      (node (ref "RPI_ZERO") (pin "21") (pinfunction "21_21") (pintype "passive"))
    )
    (net (code "82") (name "unconnected-(RPI_ZERO-Pad23)") (class "Default")
      (node (ref "RPI_ZERO") (pin "23") (pinfunction "23_23") (pintype "passive"))
    )
    (net (code "83") (name "unconnected-(RPI_ZERO-Pad25)") (class "Default")
      (node (ref "RPI_ZERO") (pin "25") (pinfunction "25_25") (pintype "passive"))
    )
    (net (code "84") (name "unconnected-(RPI_ZERO-Pad27)") (class "Default")
      (node (ref "RPI_ZERO") (pin "27") (pinfunction "27_27") (pintype "passive"))
    )
    (net (code "85") (name "unconnected-(RPI_ZERO-Pad29)") (class "Default")
      (node (ref "RPI_ZERO") (pin "29") (pinfunction "29_29") (pintype "passive"))
    )
    (net (code "86") (name "unconnected-(RPI_ZERO-Pad30)") (class "Default")
      (node (ref "RPI_ZERO") (pin "30") (pinfunction "30_30") (pintype "passive"))
    )
    (net (code "87") (name "unconnected-(RPI_ZERO-Pad33)") (class "Default")
      (node (ref "RPI_ZERO") (pin "33") (pinfunction "33_33") (pintype "passive"))
    )
    (net (code "88") (name "unconnected-(RPI_ZERO-Pad35)") (class "Default")
      (node (ref "RPI_ZERO") (pin "35") (pinfunction "35_35") (pintype "passive"))
    )
    (net (code "89") (name "unconnected-(RPI_ZERO-Pad37)") (class "Default")
      (node (ref "RPI_ZERO") (pin "37") (pinfunction "37_37") (pintype "passive"))
    )
    (net (code "90") (name "unconnected-(RPI_ZERO-Pad39)") (class "Default")
      (node (ref "RPI_ZERO") (pin "39") (pinfunction "39_39") (pintype "passive"))
    )
    (net (code "91") (name "unconnected-(STM32F103CB-PA1-Pad11)") (class "Default")
      (node (ref "STM32F103CB") (pin "11") (pinfunction "PA1_11") (pintype "bidirectional"))
    )
    (net (code "92") (name "unconnected-(STM32F103CB-PA8-Pad29)") (class "Default")
      (node (ref "STM32F103CB") (pin "29") (pinfunction "PA8_29") (pintype "bidirectional"))
    )
    (net (code "93") (name "unconnected-(STM32F103CB-PB2-Pad20)") (class "Default")
      (node (ref "STM32F103CB") (pin "20") (pinfunction "PB2_20") (pintype "bidirectional"))
    )
    (net (code "94") (name "unconnected-(STM32F103CB-PB4-Pad40)") (class "Default")
      (node (ref "STM32F103CB") (pin "40") (pinfunction "PB4_40") (pintype "bidirectional"))
    )
    (net (code "95") (name "unconnected-(STM32F103CB-PB8-Pad45)") (class "Default")
      (node (ref "STM32F103CB") (pin "45") (pinfunction "PB8_45") (pintype "bidirectional"))
    )
    (net (code "96") (name "unconnected-(STM32F103CB-PB9-Pad46)") (class "Default")
      (node (ref "STM32F103CB") (pin "46") (pinfunction "PB9_46") (pintype "bidirectional"))
    )
    (net (code "97") (name "unconnected-(STM32F103CB-PB13-Pad26)") (class "Default")
      (node (ref "STM32F103CB") (pin "26") (pinfunction "PB13_26") (pintype "bidirectional"))
    )
    (net (code "98") (name "unconnected-(STM32F103CB-PC14-OSC32_IN-Pad3)") (class "Default")
      (node (ref "STM32F103CB") (pin "3") (pinfunction "PC14-OSC32_IN_3") (pintype "bidirectional"))
    )
    (net (code "99") (name "unconnected-(STM32F103CB-PC15-OSC32_OUT-Pad4)") (class "Default")
      (node (ref "STM32F103CB") (pin "4") (pinfunction "PC15-OSC32_OUT_4") (pintype "bidirectional"))
    )
  )
)
